# RE-MB-V2_1.net
KiCad netlist of a schematic drawn in EAGLE
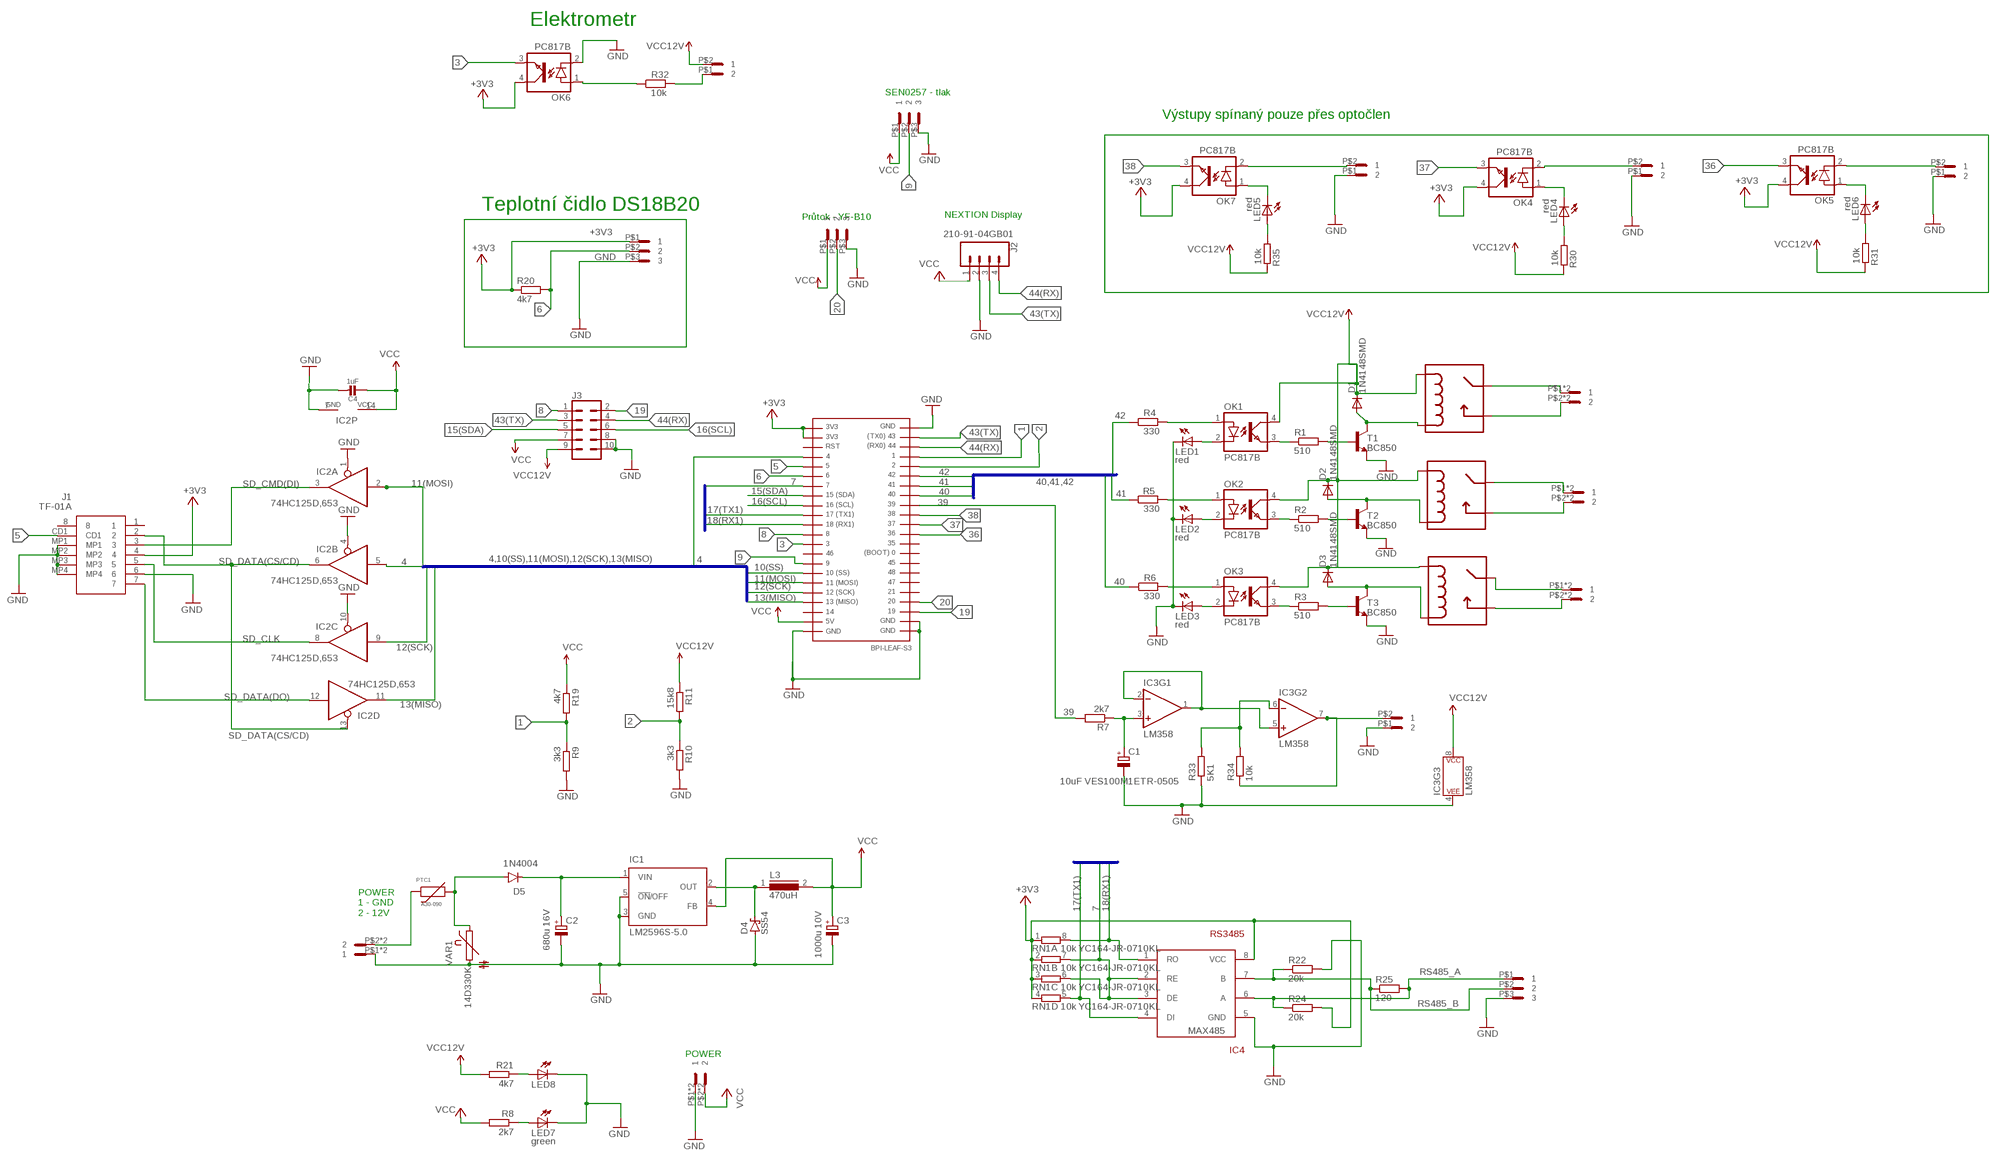
[diagram p0: schematic, sheet 1]

(export (version "E")
  (design (tool "Eeschema 10.0.6"))
  (components
    (comp (ref "BPI")
      (value "BPI-LEAF-S3")
      (footprint "eagle-import:BPI-LEAF-S3")
      (libsource (lib "eagle-import") (part "BPI-LEAF-S3"))
    )
    (comp (ref "C1")
      (value "10uF VES100M1ETR-0505")
      (footprint "eagle-import:PANASONIC_C")
      (libsource (lib "eagle-import") (part "resistor_348_CPOL-EUC"))
    )
    (comp (ref "C2")
      (value "680u 16V")
      (footprint "eagle-import:153CLV-1010")
      (libsource (lib "eagle-import") (part "CPOL-EU153CLV-1010"))
    )
    (comp (ref "C3")
      (value "1000u 10V")
      (footprint "eagle-import:153CLV-1010")
      (libsource (lib "eagle-import") (part "CPOL-EU153CLV-1010"))
    )
    (comp (ref "C4")
      (value "1uF")
      (footprint "eagle-import:0805-NO")
      (libsource (lib "eagle-import") (part "CAP_CERAMIC0805-NOOUTLINE"))
    )
    (comp (ref "D1")
      (value "1N4148SMD")
      (footprint "eagle-import:DO214AC")
      (libsource (lib "eagle-import") (part "1N4148SMD"))
    )
    (comp (ref "D2")
      (value "1N4148SMD")
      (footprint "eagle-import:DO214AC")
      (libsource (lib "eagle-import") (part "1N4148SMD"))
    )
    (comp (ref "D3")
      (value "1N4148SMD")
      (footprint "eagle-import:DO214AC")
      (libsource (lib "eagle-import") (part "1N4148SMD"))
    )
    (comp (ref "D4")
      (value "SS54")
      (footprint "eagle-import:SMB")
      (libsource (lib "eagle-import") (part "MBRS130LT3"))
    )
    (comp (ref "D5")
      (value "1N4004")
      (footprint "eagle-import:DO41-10")
      (libsource (lib "eagle-import") (part "1N4004"))
    )
    (comp (ref "IC1")
      (value "LM2596S-5.0")
      (footprint "eagle-import:TO263-5")
      (fields (field (name "MF") "NATIONAL SEMICONDUCTOR") (field (name "MPN") "LM2596S-ADJ/NOPB"))
      (libsource (lib "eagle-import") (part "LM2596S"))
    )
    (comp (ref "IC2")
      (value "74HC125D,653")
      (footprint "eagle-import:SO14")
      (fields (field (name "SPICEPREFIX") "J"))
      (libsource (lib "eagle-import") (part "74125DHC"))
    )
    (comp (ref "IC3")
      (value "LM358")
      (footprint "eagle-import:SO08")
      (libsource (lib "eagle-import") (part "OPAMP-DUALU"))
    )
    (comp (ref "IC4")
      (value "RS3485")
      (footprint "eagle-import:MAX485")
      (libsource (lib "eagle-import") (part "MAX485MAX485ESA"))
    )
    (comp (ref "J1")
      (value "TF-01A")
      (footprint "eagle-import:TF01A")
      (libsource (lib "eagle-import") (part "TF-01A"))
    )
    (comp (ref "J2")
      (value "210-91-04GB01")
      (footprint "eagle-import:1X04")
      (libsource (lib "eagle-import") (part "CONN_04"))
    )
    (comp (ref "J3")
      (value "CONN_05X2RAF")
      (footprint "eagle-import:2X5-RAF")
      (libsource (lib "eagle-import") (part "CONN_05X2RAF"))
    )
    (comp (ref "K1")
      (value "HF49FD/012-1H11")
      (footprint "eagle-import:HF49FD_024-1H11")
      (libsource (lib "eagle-import") (part "HF49FD/024-1H11"))
    )
    (comp (ref "K2")
      (value "HF49FD/012-1H11")
      (footprint "eagle-import:HF49FD_024-1H11")
      (libsource (lib "eagle-import") (part "HF49FD/024-1H11"))
    )
    (comp (ref "K3")
      (value "HF49FD/012-1H11")
      (footprint "eagle-import:HF49FD_024-1H11")
      (libsource (lib "eagle-import") (part "HF49FD/024-1H11"))
    )
    (comp (ref "L3")
      (value "470uH")
      (footprint "eagle-import:DR127")
      (libsource (lib "eagle-import") (part "DR127"))
    )
    (comp (ref "LED1")
      (value "red")
      (footprint "eagle-import:CHIPLED_0805")
      (libsource (lib "eagle-import") (part "LEDCHIPLED_0805"))
    )
    (comp (ref "LED2")
      (value "red")
      (footprint "eagle-import:CHIPLED_0805")
      (libsource (lib "eagle-import") (part "LEDCHIPLED_0805"))
    )
    (comp (ref "LED3")
      (value "red")
      (footprint "eagle-import:CHIPLED_0805")
      (libsource (lib "eagle-import") (part "LEDCHIPLED_0805"))
    )
    (comp (ref "LED4")
      (value "red")
      (footprint "eagle-import:CHIPLED_0805")
      (libsource (lib "eagle-import") (part "LEDCHIPLED_0805"))
    )
    (comp (ref "LED5")
      (value "red")
      (footprint "eagle-import:CHIPLED_0805")
      (libsource (lib "eagle-import") (part "LEDCHIPLED_0805"))
    )
    (comp (ref "LED6")
      (value "red")
      (footprint "eagle-import:CHIPLED_0805")
      (libsource (lib "eagle-import") (part "LEDCHIPLED_0805"))
    )
    (comp (ref "LED7")
      (value "green")
      (footprint "eagle-import:CHIPLED_0805")
      (libsource (lib "eagle-import") (part "LEDCHIPLED_0805"))
    )
    (comp (ref "LED8")
      (value "green")
      (footprint "eagle-import:CHIPLED_0805")
      (libsource (lib "eagle-import") (part "LEDCHIPLED_0805"))
    )
    (comp (ref "OK1")
      (value "PC817B")
      (footprint "eagle-import:DIL04")
      (fields (field (name "MPN") "PC817X4J000F"))
      (libsource (lib "eagle-import") (part "PC817"))
    )
    (comp (ref "OK2")
      (value "PC817B")
      (footprint "eagle-import:DIL04")
      (fields (field (name "MPN") "PC817X4J000F"))
      (libsource (lib "eagle-import") (part "PC817"))
    )
    (comp (ref "OK3")
      (value "PC817B")
      (footprint "eagle-import:DIL04")
      (fields (field (name "MPN") "PC817X4J000F"))
      (libsource (lib "eagle-import") (part "PC817"))
    )
    (comp (ref "OK4")
      (value "PC817B")
      (footprint "eagle-import:DIL04")
      (fields (field (name "MPN") "PC817X4J000F"))
      (libsource (lib "eagle-import") (part "PC817"))
    )
    (comp (ref "OK5")
      (value "PC817B")
      (footprint "eagle-import:DIL04")
      (fields (field (name "MPN") "PC817X4J000F"))
      (libsource (lib "eagle-import") (part "PC817"))
    )
    (comp (ref "OK6")
      (value "PC817B")
      (footprint "eagle-import:DIL04")
      (fields (field (name "MPN") "PC817X4J000F"))
      (libsource (lib "eagle-import") (part "PC817"))
    )
    (comp (ref "OK7")
      (value "PC817B")
      (footprint "eagle-import:DIL04")
      (fields (field (name "MPN") "PC817X4J000F"))
      (libsource (lib "eagle-import") (part "PC817"))
    )
    (comp (ref "PTC1")
      (value "A30-090")
      (footprint "eagle-import:PK250-240")
      (libsource (lib "eagle-import") (part "TERMISTORPK250-240"))
    )
    (comp (ref "R1")
      (value "510")
      (footprint "eagle-import:M0805")
      (libsource (lib "eagle-import") (part "resistor_348_R-EU_M0805"))
    )
    (comp (ref "R2")
      (value "510")
      (footprint "eagle-import:M0805")
      (libsource (lib "eagle-import") (part "resistor_348_R-EU_M0805"))
    )
    (comp (ref "R3")
      (value "510")
      (footprint "eagle-import:M0805")
      (libsource (lib "eagle-import") (part "resistor_348_R-EU_M0805"))
    )
    (comp (ref "R4")
      (value "330")
      (footprint "eagle-import:M0805")
      (libsource (lib "eagle-import") (part "resistor_348_R-EU_M0805"))
    )
    (comp (ref "R5")
      (value "330")
      (footprint "eagle-import:M0805")
      (libsource (lib "eagle-import") (part "resistor_348_R-EU_M0805"))
    )
    (comp (ref "R6")
      (value "330")
      (footprint "eagle-import:M0805")
      (libsource (lib "eagle-import") (part "resistor_348_R-EU_M0805"))
    )
    (comp (ref "R7")
      (value "2k7")
      (footprint "eagle-import:R0805")
      (libsource (lib "eagle-import") (part "R-EU_R0805"))
    )
    (comp (ref "R8")
      (value "2k7")
      (footprint "eagle-import:M0805")
      (libsource (lib "eagle-import") (part "resistor_348_R-EU_M0805"))
    )
    (comp (ref "R9")
      (value "3k3")
      (footprint "eagle-import:M0805")
      (libsource (lib "eagle-import") (part "resistor_348_R-EU_M0805"))
    )
    (comp (ref "R10")
      (value "3k3")
      (footprint "eagle-import:M0805")
      (libsource (lib "eagle-import") (part "resistor_348_R-EU_M0805"))
    )
    (comp (ref "R11")
      (value "15k8")
      (footprint "eagle-import:M0805")
      (libsource (lib "eagle-import") (part "resistor_348_R-EU_M0805"))
    )
    (comp (ref "R19")
      (value "4k7")
      (footprint "eagle-import:M0805")
      (libsource (lib "eagle-import") (part "resistor_348_R-EU_M0805"))
    )
    (comp (ref "R20")
      (value "4k7")
      (footprint "eagle-import:M0805")
      (libsource (lib "eagle-import") (part "resistor_348_R-EU_M0805"))
    )
    (comp (ref "R21")
      (value "4k7")
      (footprint "eagle-import:M0805")
      (libsource (lib "eagle-import") (part "resistor_348_R-EU_M0805"))
    )
    (comp (ref "R22")
      (value "20k")
      (footprint "eagle-import:R0805")
      (libsource (lib "eagle-import") (part "resistor_348_R-EU_R0805"))
    )
    (comp (ref "R24")
      (value "20k")
      (footprint "eagle-import:R0805")
      (libsource (lib "eagle-import") (part "resistor_348_R-EU_R0805"))
    )
    (comp (ref "R25")
      (value "120")
      (footprint "eagle-import:R0805")
      (libsource (lib "eagle-import") (part "resistor_348_R-EU_R0805"))
    )
    (comp (ref "R30")
      (value "10k")
      (footprint "eagle-import:M0805")
      (libsource (lib "eagle-import") (part "resistor_348_R-EU_M0805"))
    )
    (comp (ref "R31")
      (value "10k")
      (footprint "eagle-import:M0805")
      (libsource (lib "eagle-import") (part "resistor_348_R-EU_M0805"))
    )
    (comp (ref "R32")
      (value "10k")
      (footprint "eagle-import:M0805")
      (libsource (lib "eagle-import") (part "resistor_348_R-EU_M0805"))
    )
    (comp (ref "R33")
      (value "5K1")
      (footprint "eagle-import:R0805")
      (libsource (lib "eagle-import") (part "R-EU_R0805"))
    )
    (comp (ref "R34")
      (value "10k")
      (footprint "eagle-import:R0805")
      (libsource (lib "eagle-import") (part "R-EU_R0805"))
    )
    (comp (ref "R35")
      (value "10k")
      (footprint "eagle-import:M0805")
      (libsource (lib "eagle-import") (part "resistor_348_R-EU_M0805"))
    )
    (comp (ref "RN1")
      (value "10k YC164-JR-0710KL")
      (footprint "eagle-import:0603-ARV")
      (libsource (lib "eagle-import") (part "4R-N0603-ARV"))
    )
    (comp (ref "T1")
      (value "BC850")
      (footprint "eagle-import:SOT23")
      (libsource (lib "eagle-import") (part "BC850"))
    )
    (comp (ref "T2")
      (value "BC850")
      (footprint "eagle-import:SOT23")
      (libsource (lib "eagle-import") (part "BC850"))
    )
    (comp (ref "T3")
      (value "BC850")
      (footprint "eagle-import:SOT23")
      (libsource (lib "eagle-import") (part "BC850"))
    )
    (comp (ref "U$2")
      (value "DG235-5.0")
      (footprint "eagle-import:DG235-5.0")
      (libsource (lib "eagle-import") (part "DG235-5.0"))
    )
    (comp (ref "U$3")
      (value "SPTA1/3-5,0")
      (footprint "eagle-import:SPTA1_3-5,0")
      (libsource (lib "eagle-import") (part "SPTA1/3-5,0"))
    )
    (comp (ref "U$4")
      (value "DG235-5.0")
      (footprint "eagle-import:DG235-5.0")
      (libsource (lib "eagle-import") (part "DG235-5.0"))
    )
    (comp (ref "U$5")
      (value "DG235-5.0")
      (footprint "eagle-import:DG235-5.0")
      (libsource (lib "eagle-import") (part "DG235-5.0"))
    )
    (comp (ref "U$6")
      (value "DG235-5.0")
      (footprint "eagle-import:DG235-5.0")
      (libsource (lib "eagle-import") (part "DG235-5.0"))
    )
    (comp (ref "U$7")
      (value "DG235-5.0")
      (footprint "eagle-import:DG235-5.0")
      (libsource (lib "eagle-import") (part "DG235-5.0"))
    )
    (comp (ref "U$8")
      (value "SPTA1/2-5,0")
      (footprint "eagle-import:SPTA1_2-5,0")
      (libsource (lib "eagle-import") (part "SPTA1/2-5,0"))
    )
    (comp (ref "U$9")
      (value "SPTA1/2-5,0")
      (footprint "eagle-import:SPTA1_2-5,0")
      (libsource (lib "eagle-import") (part "SPTA1/2-5,0"))
    )
    (comp (ref "U$10")
      (value "SPTA1/3-5,0")
      (footprint "eagle-import:SPTA1_3-5,0")
      (libsource (lib "eagle-import") (part "SPTA1/3-5,0"))
    )
    (comp (ref "U$12")
      (value "SPTA1/3-5,0")
      (footprint "eagle-import:SPTA1_3-5,0")
      (libsource (lib "eagle-import") (part "SPTA1/3-5,0"))
    )
    (comp (ref "U$13")
      (value "SPTA1/2-5,0")
      (footprint "eagle-import:SPTA1_2-5,0")
      (libsource (lib "eagle-import") (part "SPTA1/2-5,0"))
    )
    (comp (ref "U$14")
      (value "SPTA1/2-5,0")
      (footprint "eagle-import:SPTA1_2-5,0")
      (libsource (lib "eagle-import") (part "SPTA1/2-5,0"))
    )
    (comp (ref "U$15")
      (value "SPTA1/2-5,0")
      (footprint "eagle-import:SPTA1_2-5,0")
      (libsource (lib "eagle-import") (part "SPTA1/2-5,0"))
    )
    (comp (ref "U$16")
      (value "SPTA1/3-5,0")
      (footprint "eagle-import:SPTA1_3-5,0")
      (libsource (lib "eagle-import") (part "SPTA1/3-5,0"))
    )
    (comp (ref "VAR1")
      (value "14D330K")
      (footprint "eagle-import:S10K11")
      (libsource (lib "eagle-import") (part "S10K11"))
    )
  )
  (nets
    (net (code "1") (name "+3V3") (class "Default")
      (node (ref "BPI") (pin "1") (pinfunction "P$1_1") (pintype "bidirectional"))
      (node (ref "BPI") (pin "2") (pinfunction "P$2_2") (pintype "bidirectional"))
      (node (ref "IC4") (pin "8") (pinfunction "VCC_8") (pintype "bidirectional"))
      (node (ref "J1") (pin "4") (pinfunction "4_4") (pintype "bidirectional"))
      (node (ref "OK4") (pin "4") (pinfunction "COL_4") (pintype "passive"))
      (node (ref "OK5") (pin "4") (pinfunction "COL_4") (pintype "passive"))
      (node (ref "OK6") (pin "4") (pinfunction "COL_4") (pintype "passive"))
      (node (ref "OK7") (pin "4") (pinfunction "COL_4") (pintype "passive"))
      (node (ref "R20") (pin "1") (pinfunction "1_1") (pintype "passive"))
      (node (ref "R24") (pin "2") (pinfunction "2_2") (pintype "passive"))
      (node (ref "RN1") (pin "1") (pinfunction "1_1") (pintype "passive"))
      (node (ref "RN1") (pin "2") (pinfunction "1_2") (pintype "passive"))
      (node (ref "RN1") (pin "3") (pinfunction "1_3") (pintype "passive"))
      (node (ref "RN1") (pin "4") (pinfunction "1_4") (pintype "passive"))
      (node (ref "U$3") (pin "P$1") (pinfunction "1_P$1") (pintype "input"))
    )
    (net (code "2") (name "/4") (class "Default")
      (node (ref "BPI") (pin "4") (pinfunction "P$4_4") (pintype "bidirectional"))
      (node (ref "IC2") (pin "5") (pinfunction "I_5") (pintype "input"))
    )
    (net (code "3") (name "/7") (class "Default")
      (node (ref "BPI") (pin "7") (pinfunction "P$7_7") (pintype "bidirectional"))
      (node (ref "IC4") (pin "2") (pinfunction "RE_2") (pintype "bidirectional"))
      (node (ref "IC4") (pin "3") (pinfunction "DE_3") (pintype "bidirectional"))
      (node (ref "RN1") (pin "6") (pinfunction "2_6") (pintype "passive"))
      (node (ref "RN1") (pin "7") (pinfunction "2_7") (pintype "passive"))
    )
    (net (code "4") (name "/10(SS)") (class "Default")
      (node (ref "BPI") (pin "16") (pinfunction "P$16_16") (pintype "bidirectional"))
    )
    (net (code "5") (name "/11(MOSI)") (class "Default")
      (node (ref "BPI") (pin "17") (pinfunction "P$17_17") (pintype "bidirectional"))
      (node (ref "IC2") (pin "2") (pinfunction "I_2") (pintype "input"))
    )
    (net (code "6") (name "/12(SCK)") (class "Default")
      (node (ref "BPI") (pin "18") (pinfunction "P$18_18") (pintype "bidirectional"))
      (node (ref "IC2") (pin "9") (pinfunction "I_9") (pintype "input"))
    )
    (net (code "7") (name "/13(MISO)") (class "Default")
      (node (ref "BPI") (pin "19") (pinfunction "P$19_19") (pintype "bidirectional"))
      (node (ref "IC2") (pin "11") (pinfunction "O_11") (pintype "tri_state"))
    )
    (net (code "8") (name "/17(TX1)") (class "Default")
      (node (ref "BPI") (pin "10") (pinfunction "P$10_10") (pintype "bidirectional"))
      (node (ref "IC4") (pin "4") (pinfunction "DI_4") (pintype "bidirectional"))
      (node (ref "RN1") (pin "5") (pinfunction "2_5") (pintype "passive"))
    )
    (net (code "9") (name "/18(RX1)") (class "Default")
      (node (ref "BPI") (pin "11") (pinfunction "P$11_11") (pintype "bidirectional"))
      (node (ref "IC4") (pin "1") (pinfunction "RO_1") (pintype "bidirectional"))
      (node (ref "RN1") (pin "8") (pinfunction "2_8") (pintype "passive"))
    )
    (net (code "10") (name "/39") (class "Default")
      (node (ref "BPI") (pin "31") (pinfunction "P$31_31") (pintype "bidirectional"))
      (node (ref "R7") (pin "2") (pinfunction "2_2") (pintype "passive"))
    )
    (net (code "11") (name "/40") (class "Default")
      (node (ref "BPI") (pin "30") (pinfunction "P$30_30") (pintype "bidirectional"))
      (node (ref "R6") (pin "1") (pinfunction "1_1") (pintype "passive"))
    )
    (net (code "12") (name "/41") (class "Default")
      (node (ref "BPI") (pin "29") (pinfunction "P$29_29") (pintype "bidirectional"))
      (node (ref "R5") (pin "1") (pinfunction "1_1") (pintype "passive"))
    )
    (net (code "13") (name "/42") (class "Default")
      (node (ref "BPI") (pin "28") (pinfunction "P$28_28") (pintype "bidirectional"))
      (node (ref "R4") (pin "1") (pinfunction "1_1") (pintype "passive"))
    )
    (net (code "14") (name "/RS485_A") (class "Default")
      (node (ref "IC4") (pin "6") (pinfunction "A_6") (pintype "bidirectional"))
      (node (ref "R24") (pin "1") (pinfunction "1_1") (pintype "passive"))
      (node (ref "R25") (pin "2") (pinfunction "2_2") (pintype "passive"))
      (node (ref "U$10") (pin "P$1") (pinfunction "1_P$1") (pintype "input"))
    )
    (net (code "15") (name "/RS485_B") (class "Default")
      (node (ref "IC4") (pin "7") (pinfunction "B_7") (pintype "bidirectional"))
      (node (ref "R22") (pin "1") (pinfunction "1_1") (pintype "passive"))
      (node (ref "R25") (pin "1") (pinfunction "1_1") (pintype "passive"))
      (node (ref "U$10") (pin "P$2") (pinfunction "2_P$2") (pintype "input"))
    )
    (net (code "16") (name "/SD_CLK") (class "Default")
      (node (ref "IC2") (pin "8") (pinfunction "O_8") (pintype "tri_state"))
      (node (ref "J1") (pin "5") (pinfunction "5_5") (pintype "bidirectional"))
    )
    (net (code "17") (name "/SD_CMD(DI)") (class "Default")
      (node (ref "IC2") (pin "3") (pinfunction "O_3") (pintype "tri_state"))
      (node (ref "J1") (pin "3") (pinfunction "3_3") (pintype "bidirectional"))
    )
    (net (code "18") (name "/SD_DATA(CS{slash}CD)") (class "Default")
      (node (ref "IC2") (pin "13") (pinfunction "OE_13") (pintype "input"))
      (node (ref "IC2") (pin "6") (pinfunction "O_6") (pintype "tri_state"))
      (node (ref "J1") (pin "2") (pinfunction "2_2") (pintype "bidirectional"))
    )
    (net (code "19") (name "/SD_DATA(DO)") (class "Default")
      (node (ref "IC2") (pin "12") (pinfunction "I_12") (pintype "input"))
      (node (ref "J1") (pin "7") (pinfunction "7_7") (pintype "bidirectional"))
    )
    (net (code "23") (name "1") (class "Default")
      (node (ref "BPI") (pin "26") (pinfunction "P$26_26") (pintype "bidirectional"))
      (node (ref "R19") (pin "2") (pinfunction "2_2") (pintype "passive"))
      (node (ref "R9") (pin "1") (pinfunction "1_1") (pintype "passive"))
    )
    (net (code "24") (name "2") (class "Default")
      (node (ref "BPI") (pin "27") (pinfunction "P$27_27") (pintype "bidirectional"))
      (node (ref "R10") (pin "1") (pinfunction "1_1") (pintype "passive"))
      (node (ref "R11") (pin "2") (pinfunction "2_2") (pintype "passive"))
    )
    (net (code "25") (name "3") (class "Default")
      (node (ref "BPI") (pin "13") (pinfunction "P$13_13") (pintype "bidirectional"))
      (node (ref "OK6") (pin "3") (pinfunction "EMIT_3") (pintype "passive"))
    )
    (net (code "26") (name "5") (class "Default")
      (node (ref "BPI") (pin "5") (pinfunction "P$5_5") (pintype "bidirectional"))
      (node (ref "J1") (pin "CD1") (pinfunction "CD1_CD1") (pintype "bidirectional"))
    )
    (net (code "27") (name "6") (class "Default")
      (node (ref "BPI") (pin "6") (pinfunction "P$6_6") (pintype "bidirectional"))
      (node (ref "R20") (pin "2") (pinfunction "2_2") (pintype "passive"))
      (node (ref "U$3") (pin "P$2") (pinfunction "2_P$2") (pintype "input"))
    )
    (net (code "28") (name "8") (class "Default")
      (node (ref "BPI") (pin "12") (pinfunction "P$12_12") (pintype "bidirectional"))
      (node (ref "J3") (pin "1") (pinfunction "1_1") (pintype "passive"))
    )
    (net (code "29") (name "9") (class "Default")
      (node (ref "BPI") (pin "15") (pinfunction "P$15_15") (pintype "bidirectional"))
      (node (ref "U$12") (pin "P$2") (pinfunction "2_P$2") (pintype "input"))
    )
    (net (code "30") (name "15(SDA)") (class "Default")
      (node (ref "BPI") (pin "8") (pinfunction "P$8_8") (pintype "bidirectional"))
      (node (ref "J3") (pin "5") (pinfunction "5_5") (pintype "passive"))
    )
    (net (code "31") (name "16(SCL)") (class "Default")
      (node (ref "BPI") (pin "9") (pinfunction "P$9_9") (pintype "bidirectional"))
      (node (ref "J3") (pin "6") (pinfunction "6_6") (pintype "passive"))
    )
    (net (code "32") (name "19") (class "Default")
      (node (ref "BPI") (pin "42") (pinfunction "P$42_42") (pintype "bidirectional"))
      (node (ref "J3") (pin "2") (pinfunction "2_2") (pintype "passive"))
    )
    (net (code "33") (name "20") (class "Default")
      (node (ref "BPI") (pin "41") (pinfunction "P$41_41") (pintype "bidirectional"))
      (node (ref "U$16") (pin "P$2") (pinfunction "2_P$2") (pintype "input"))
    )
    (net (code "34") (name "36") (class "Default")
      (node (ref "BPI") (pin "34") (pinfunction "P$34_34") (pintype "bidirectional"))
      (node (ref "OK5") (pin "3") (pinfunction "EMIT_3") (pintype "passive"))
    )
    (net (code "35") (name "37") (class "Default")
      (node (ref "BPI") (pin "33") (pinfunction "P$33_33") (pintype "bidirectional"))
      (node (ref "OK4") (pin "3") (pinfunction "EMIT_3") (pintype "passive"))
    )
    (net (code "36") (name "38") (class "Default")
      (node (ref "BPI") (pin "32") (pinfunction "P$32_32") (pintype "bidirectional"))
      (node (ref "OK7") (pin "3") (pinfunction "EMIT_3") (pintype "passive"))
    )
    (net (code "37") (name "43(TX)") (class "Default")
      (node (ref "BPI") (pin "24") (pinfunction "P$24_24") (pintype "bidirectional"))
      (node (ref "J2") (pin "3") (pinfunction "3_3") (pintype "passive"))
      (node (ref "J3") (pin "3") (pinfunction "3_3") (pintype "passive"))
    )
    (net (code "38") (name "44(RX)") (class "Default")
      (node (ref "BPI") (pin "25") (pinfunction "P$25_25") (pintype "bidirectional"))
      (node (ref "J2") (pin "4") (pinfunction "4_4") (pintype "passive"))
      (node (ref "J3") (pin "4") (pinfunction "4_4") (pintype "passive"))
    )
    (net (code "39") (name "GND") (class "Default")
      (node (ref "BPI") (pin "22") (pinfunction "P$22_22") (pintype "bidirectional"))
      (node (ref "BPI") (pin "23") (pinfunction "P$23_23") (pintype "bidirectional"))
      (node (ref "BPI") (pin "43") (pinfunction "P$43_43") (pintype "bidirectional"))
      (node (ref "BPI") (pin "44") (pinfunction "P$44_44") (pintype "bidirectional"))
      (node (ref "C1") (pin "-") (pinfunction "-_-") (pintype "passive"))
      (node (ref "C2") (pin "-") (pinfunction "-_-") (pintype "passive"))
      (node (ref "C3") (pin "-") (pinfunction "-_-") (pintype "passive"))
      (node (ref "C4") (pin "2") (pinfunction "2_2") (pintype "passive"))
      (node (ref "D4") (pin "A") (pinfunction "A_A") (pintype "passive"))
      (node (ref "IC1") (pin "3") (pinfunction "GND_3") (pintype "power_in"))
      (node (ref "IC1") (pin "5") (pinfunction "~{ON}/OFF_5") (pintype "input"))
      (node (ref "IC2") (pin "1") (pinfunction "OE_1") (pintype "input"))
      (node (ref "IC2") (pin "10") (pinfunction "OE_10") (pintype "input"))
      (node (ref "IC2") (pin "4") (pinfunction "OE_4") (pintype "input"))
      (node (ref "IC2") (pin "7") (pinfunction "GND_7") (pintype "power_in"))
      (node (ref "IC3") (pin "4") (pinfunction "P$V-_4") (pintype "bidirectional"))
      (node (ref "IC4") (pin "5") (pinfunction "GND_5") (pintype "bidirectional"))
      (node (ref "J1") (pin "6") (pinfunction "6_6") (pintype "bidirectional"))
      (node (ref "J1") (pin "MP1") (pinfunction "MP1_MP1") (pintype "bidirectional"))
      (node (ref "J1") (pin "MP2") (pinfunction "MP2_MP2") (pintype "bidirectional"))
      (node (ref "J1") (pin "MP3") (pinfunction "MP3_MP3") (pintype "bidirectional"))
      (node (ref "J1") (pin "MP4") (pinfunction "MP4_MP4") (pintype "bidirectional"))
      (node (ref "J2") (pin "2") (pinfunction "2_2") (pintype "passive"))
      (node (ref "J3") (pin "10") (pinfunction "10_10") (pintype "passive"))
      (node (ref "J3") (pin "8") (pinfunction "8_8") (pintype "passive"))
      (node (ref "LED1") (pin "C") (pinfunction "C_C") (pintype "passive"))
      (node (ref "LED2") (pin "C") (pinfunction "C_C") (pintype "passive"))
      (node (ref "LED3") (pin "C") (pinfunction "C_C") (pintype "passive"))
      (node (ref "LED7") (pin "C") (pinfunction "C_C") (pintype "passive"))
      (node (ref "LED8") (pin "C") (pinfunction "C_C") (pintype "passive"))
      (node (ref "OK6") (pin "2") (pinfunction "C_2") (pintype "passive"))
      (node (ref "R10") (pin "2") (pinfunction "2_2") (pintype "passive"))
      (node (ref "R22") (pin "2") (pinfunction "2_2") (pintype "passive"))
      (node (ref "R33") (pin "1") (pinfunction "1_1") (pintype "passive"))
      (node (ref "R9") (pin "2") (pinfunction "2_2") (pintype "passive"))
      (node (ref "T1") (pin "2") (pinfunction "E_2") (pintype "passive"))
      (node (ref "T2") (pin "2") (pinfunction "E_2") (pintype "passive"))
      (node (ref "T3") (pin "2") (pinfunction "E_2") (pintype "passive"))
      (node (ref "U$10") (pin "P$3") (pinfunction "3_P$3") (pintype "input"))
      (node (ref "U$12") (pin "P$3") (pinfunction "3_P$3") (pintype "input"))
      (node (ref "U$13") (pin "P$1") (pinfunction "2_P$1") (pintype "input"))
      (node (ref "U$14") (pin "P$1") (pinfunction "2_P$1") (pintype "input"))
      (node (ref "U$15") (pin "P$1") (pinfunction "2_P$1") (pintype "input"))
      (node (ref "U$16") (pin "P$3") (pinfunction "3_P$3") (pintype "input"))
      (node (ref "U$2") (pin "P$1") (pinfunction "1_P$1") (pintype "input"))
      (node (ref "U$2") (pin "P$3") (pinfunction "1_P$3") (pintype "input"))
      (node (ref "U$3") (pin "P$3") (pinfunction "3_P$3") (pintype "input"))
      (node (ref "U$6") (pin "P$1") (pinfunction "1_P$1") (pintype "input"))
      (node (ref "U$6") (pin "P$3") (pinfunction "1_P$3") (pintype "input"))
      (node (ref "U$8") (pin "P$1") (pinfunction "2_P$1") (pintype "input"))
      (node (ref "VAR1") (pin "2") (pinfunction "2_2") (pintype "passive"))
    )
    (net (code "40") (name "Net-(D5-PadA)") (class "Default")
      (node (ref "D5") (pin "A") (pinfunction "A_A") (pintype "passive"))
      (node (ref "PTC1") (pin "P$2") (pinfunction "P$2_P$2") (pintype "bidirectional"))
      (node (ref "VAR1") (pin "1") (pinfunction "1_1") (pintype "passive"))
    )
    (net (code "41") (name "Net-(IC1-OUT)") (class "Default")
      (node (ref "D4") (pin "C") (pinfunction "C_C") (pintype "passive"))
      (node (ref "IC1") (pin "2") (pinfunction "OUT_2") (pintype "output"))
      (node (ref "L3") (pin "1") (pinfunction "1_1") (pintype "passive"))
    )
    (net (code "42") (name "Net-(IC3A-+IN)") (class "Default")
      (node (ref "C1") (pin "+") (pinfunction "+_+") (pintype "passive"))
      (node (ref "IC3") (pin "3") (pinfunction "+IN_3") (pintype "input"))
      (node (ref "R7") (pin "1") (pinfunction "1_1") (pintype "passive"))
    )
    (net (code "43") (name "Net-(IC3A--IN)") (class "Default")
      (node (ref "IC3") (pin "1") (pinfunction "OUT_1") (pintype "output"))
      (node (ref "IC3") (pin "2") (pinfunction "-IN_2") (pintype "input"))
      (node (ref "IC3") (pin "5") (pinfunction "+IN_5") (pintype "input"))
    )
    (net (code "44") (name "Net-(IC3B--IN)") (class "Default")
      (node (ref "IC3") (pin "6") (pinfunction "-IN_6") (pintype "input"))
      (node (ref "R33") (pin "2") (pinfunction "2_2") (pintype "passive"))
      (node (ref "R34") (pin "2") (pinfunction "2_2") (pintype "passive"))
    )
    (net (code "45") (name "Net-(IC3B-OUT)") (class "Default")
      (node (ref "IC3") (pin "7") (pinfunction "OUT_7") (pintype "output"))
      (node (ref "R34") (pin "1") (pinfunction "1_1") (pintype "passive"))
      (node (ref "U$8") (pin "P$2") (pinfunction "1_P$2") (pintype "input"))
    )
    (net (code "46") (name "Net-(K1-PadP$1)") (class "Default")
      (node (ref "K1") (pin "P$1") (pinfunction "P$1_P$1") (pintype "output"))
      (node (ref "U$4") (pin "P$1") (pinfunction "1_P$1") (pintype "input"))
      (node (ref "U$4") (pin "P$3") (pinfunction "1_P$3") (pintype "input"))
    )
    (net (code "47") (name "Net-(K1-PadP$2)") (class "Default")
      (node (ref "K1") (pin "P$2") (pinfunction "P$2_P$2") (pintype "output"))
      (node (ref "U$4") (pin "P$2") (pinfunction "2_P$2") (pintype "input"))
      (node (ref "U$4") (pin "P$4") (pinfunction "2_P$4") (pintype "input"))
    )
    (net (code "48") (name "Net-(K2-PadP$1)") (class "Default")
      (node (ref "K2") (pin "P$1") (pinfunction "P$1_P$1") (pintype "output"))
      (node (ref "U$5") (pin "P$1") (pinfunction "1_P$1") (pintype "input"))
      (node (ref "U$5") (pin "P$3") (pinfunction "1_P$3") (pintype "input"))
    )
    (net (code "49") (name "Net-(K2-PadP$2)") (class "Default")
      (node (ref "K2") (pin "P$2") (pinfunction "P$2_P$2") (pintype "output"))
      (node (ref "U$5") (pin "P$2") (pinfunction "2_P$2") (pintype "input"))
      (node (ref "U$5") (pin "P$4") (pinfunction "2_P$4") (pintype "input"))
    )
    (net (code "50") (name "Net-(K3-PadP$1)") (class "Default")
      (node (ref "K3") (pin "P$1") (pinfunction "P$1_P$1") (pintype "output"))
      (node (ref "U$7") (pin "P$1") (pinfunction "1_P$1") (pintype "input"))
      (node (ref "U$7") (pin "P$3") (pinfunction "1_P$3") (pintype "input"))
    )
    (net (code "51") (name "Net-(K3-PadP$2)") (class "Default")
      (node (ref "K3") (pin "P$2") (pinfunction "P$2_P$2") (pintype "output"))
      (node (ref "U$7") (pin "P$2") (pinfunction "2_P$2") (pintype "input"))
      (node (ref "U$7") (pin "P$4") (pinfunction "2_P$4") (pintype "input"))
    )
    (net (code "52") (name "Net-(LED4-PadA)") (class "Default")
      (node (ref "LED4") (pin "A") (pinfunction "A_A") (pintype "passive"))
      (node (ref "R30") (pin "1") (pinfunction "1_1") (pintype "passive"))
    )
    (net (code "53") (name "Net-(LED5-PadA)") (class "Default")
      (node (ref "LED5") (pin "A") (pinfunction "A_A") (pintype "passive"))
      (node (ref "R35") (pin "1") (pinfunction "1_1") (pintype "passive"))
    )
    (net (code "54") (name "Net-(LED6-PadA)") (class "Default")
      (node (ref "LED6") (pin "A") (pinfunction "A_A") (pintype "passive"))
      (node (ref "R31") (pin "1") (pinfunction "1_1") (pintype "passive"))
    )
    (net (code "55") (name "Net-(LED7-PadA)") (class "Default")
      (node (ref "LED7") (pin "A") (pinfunction "A_A") (pintype "passive"))
      (node (ref "R8") (pin "1") (pinfunction "1_1") (pintype "passive"))
    )
    (net (code "56") (name "Net-(LED8-PadA)") (class "Default")
      (node (ref "LED8") (pin "A") (pinfunction "A_A") (pintype "passive"))
      (node (ref "R21") (pin "1") (pinfunction "1_1") (pintype "passive"))
    )
    (net (code "57") (name "Net-(OK1-A)") (class "Default")
      (node (ref "OK1") (pin "1") (pinfunction "A_1") (pintype "passive"))
      (node (ref "R4") (pin "2") (pinfunction "2_2") (pintype "passive"))
    )
    (net (code "58") (name "Net-(OK1-C)") (class "Default")
      (node (ref "LED1") (pin "A") (pinfunction "A_A") (pintype "passive"))
      (node (ref "OK1") (pin "2") (pinfunction "C_2") (pintype "passive"))
    )
    (net (code "59") (name "Net-(OK1-EMIT)") (class "Default")
      (node (ref "OK1") (pin "3") (pinfunction "EMIT_3") (pintype "passive"))
      (node (ref "R1") (pin "1") (pinfunction "1_1") (pintype "passive"))
    )
    (net (code "60") (name "Net-(OK2-A)") (class "Default")
      (node (ref "OK2") (pin "1") (pinfunction "A_1") (pintype "passive"))
      (node (ref "R5") (pin "2") (pinfunction "2_2") (pintype "passive"))
    )
    (net (code "61") (name "Net-(OK2-C)") (class "Default")
      (node (ref "LED2") (pin "A") (pinfunction "A_A") (pintype "passive"))
      (node (ref "OK2") (pin "2") (pinfunction "C_2") (pintype "passive"))
    )
    (net (code "62") (name "Net-(OK2-EMIT)") (class "Default")
      (node (ref "OK2") (pin "3") (pinfunction "EMIT_3") (pintype "passive"))
      (node (ref "R2") (pin "1") (pinfunction "1_1") (pintype "passive"))
    )
    (net (code "63") (name "Net-(OK3-A)") (class "Default")
      (node (ref "OK3") (pin "1") (pinfunction "A_1") (pintype "passive"))
      (node (ref "R6") (pin "2") (pinfunction "2_2") (pintype "passive"))
    )
    (net (code "64") (name "Net-(OK3-C)") (class "Default")
      (node (ref "LED3") (pin "A") (pinfunction "A_A") (pintype "passive"))
      (node (ref "OK3") (pin "2") (pinfunction "C_2") (pintype "passive"))
    )
    (net (code "65") (name "Net-(OK3-EMIT)") (class "Default")
      (node (ref "OK3") (pin "3") (pinfunction "EMIT_3") (pintype "passive"))
      (node (ref "R3") (pin "1") (pinfunction "1_1") (pintype "passive"))
    )
    (net (code "66") (name "Net-(OK4-A)") (class "Default")
      (node (ref "LED4") (pin "C") (pinfunction "C_C") (pintype "passive"))
      (node (ref "OK4") (pin "1") (pinfunction "A_1") (pintype "passive"))
    )
    (net (code "67") (name "Net-(OK4-C)") (class "Default")
      (node (ref "OK4") (pin "2") (pinfunction "C_2") (pintype "passive"))
      (node (ref "U$13") (pin "P$2") (pinfunction "1_P$2") (pintype "input"))
    )
    (net (code "68") (name "Net-(OK5-A)") (class "Default")
      (node (ref "LED6") (pin "C") (pinfunction "C_C") (pintype "passive"))
      (node (ref "OK5") (pin "1") (pinfunction "A_1") (pintype "passive"))
    )
    (net (code "69") (name "Net-(OK5-C)") (class "Default")
      (node (ref "OK5") (pin "2") (pinfunction "C_2") (pintype "passive"))
      (node (ref "U$14") (pin "P$2") (pinfunction "1_P$2") (pintype "input"))
    )
    (net (code "70") (name "Net-(OK6-A)") (class "Default")
      (node (ref "OK6") (pin "1") (pinfunction "A_1") (pintype "passive"))
      (node (ref "R32") (pin "1") (pinfunction "1_1") (pintype "passive"))
    )
    (net (code "71") (name "Net-(OK7-A)") (class "Default")
      (node (ref "LED5") (pin "C") (pinfunction "C_C") (pintype "passive"))
      (node (ref "OK7") (pin "1") (pinfunction "A_1") (pintype "passive"))
    )
    (net (code "72") (name "Net-(OK7-C)") (class "Default")
      (node (ref "OK7") (pin "2") (pinfunction "C_2") (pintype "passive"))
      (node (ref "U$15") (pin "P$2") (pinfunction "1_P$2") (pintype "input"))
    )
    (net (code "73") (name "Net-(PTC1-PadP$1)") (class "Default")
      (node (ref "PTC1") (pin "P$1") (pinfunction "P$1_P$1") (pintype "bidirectional"))
      (node (ref "U$2") (pin "P$2") (pinfunction "2_P$2") (pintype "input"))
      (node (ref "U$2") (pin "P$4") (pinfunction "2_P$4") (pintype "input"))
    )
    (net (code "74") (name "Net-(T1-B)") (class "Default")
      (node (ref "R1") (pin "2") (pinfunction "2_2") (pintype "passive"))
      (node (ref "T1") (pin "1") (pinfunction "B_1") (pintype "passive"))
    )
    (net (code "75") (name "Net-(T1-C)") (class "Default")
      (node (ref "D1") (pin "A") (pinfunction "A_A") (pintype "passive"))
      (node (ref "K1") (pin "P$4") (pinfunction "P$4_P$4") (pintype "input"))
      (node (ref "T1") (pin "3") (pinfunction "C_3") (pintype "passive"))
    )
    (net (code "76") (name "Net-(T2-B)") (class "Default")
      (node (ref "R2") (pin "2") (pinfunction "2_2") (pintype "passive"))
      (node (ref "T2") (pin "1") (pinfunction "B_1") (pintype "passive"))
    )
    (net (code "77") (name "Net-(T2-C)") (class "Default")
      (node (ref "D2") (pin "A") (pinfunction "A_A") (pintype "passive"))
      (node (ref "K2") (pin "P$4") (pinfunction "P$4_P$4") (pintype "input"))
      (node (ref "T2") (pin "3") (pinfunction "C_3") (pintype "passive"))
    )
    (net (code "78") (name "Net-(T3-B)") (class "Default")
      (node (ref "R3") (pin "2") (pinfunction "2_2") (pintype "passive"))
      (node (ref "T3") (pin "1") (pinfunction "B_1") (pintype "passive"))
    )
    (net (code "79") (name "Net-(T3-C)") (class "Default")
      (node (ref "D3") (pin "A") (pinfunction "A_A") (pintype "passive"))
      (node (ref "K3") (pin "P$4") (pinfunction "P$4_P$4") (pintype "input"))
      (node (ref "T3") (pin "3") (pinfunction "C_3") (pintype "passive"))
    )
    (net (code "80") (name "Net-(U$9-2)") (class "Default")
      (node (ref "R32") (pin "2") (pinfunction "2_2") (pintype "passive"))
      (node (ref "U$9") (pin "P$1") (pinfunction "2_P$1") (pintype "input"))
    )
    (net (code "81") (name "VCC") (class "Default")
      (node (ref "BPI") (pin "21") (pinfunction "P$21_21") (pintype "bidirectional"))
      (node (ref "C3") (pin "+") (pinfunction "+_+") (pintype "passive"))
      (node (ref "C4") (pin "1") (pinfunction "1_1") (pintype "passive"))
      (node (ref "IC1") (pin "4") (pinfunction "FB_4") (pintype "input"))
      (node (ref "IC2") (pin "14") (pinfunction "VCC_14") (pintype "power_in"))
      (node (ref "J2") (pin "1") (pinfunction "1_1") (pintype "passive"))
      (node (ref "J3") (pin "7") (pinfunction "7_7") (pintype "passive"))
      (node (ref "L3") (pin "2") (pinfunction "2_2") (pintype "passive"))
      (node (ref "R19") (pin "1") (pinfunction "1_1") (pintype "passive"))
      (node (ref "R8") (pin "2") (pinfunction "2_2") (pintype "passive"))
      (node (ref "U$12") (pin "P$1") (pinfunction "1_P$1") (pintype "input"))
      (node (ref "U$16") (pin "P$1") (pinfunction "1_P$1") (pintype "input"))
      (node (ref "U$6") (pin "P$2") (pinfunction "2_P$2") (pintype "input"))
      (node (ref "U$6") (pin "P$4") (pinfunction "2_P$4") (pintype "input"))
    )
    (net (code "82") (name "VCC12V") (class "Default")
      (node (ref "C2") (pin "+") (pinfunction "+_+") (pintype "passive"))
      (node (ref "D1") (pin "C") (pinfunction "C_C") (pintype "passive"))
      (node (ref "D2") (pin "C") (pinfunction "C_C") (pintype "passive"))
      (node (ref "D3") (pin "C") (pinfunction "C_C") (pintype "passive"))
      (node (ref "D5") (pin "C") (pinfunction "C_C") (pintype "passive"))
      (node (ref "IC1") (pin "1") (pinfunction "VIN_1") (pintype "input"))
      (node (ref "IC3") (pin "8") (pinfunction "P$V+_8") (pintype "bidirectional"))
      (node (ref "J3") (pin "9") (pinfunction "9_9") (pintype "passive"))
      (node (ref "K1") (pin "P$3") (pinfunction "P$3_P$3") (pintype "input"))
      (node (ref "K2") (pin "P$3") (pinfunction "P$3_P$3") (pintype "input"))
      (node (ref "K3") (pin "P$3") (pinfunction "P$3_P$3") (pintype "input"))
      (node (ref "OK1") (pin "4") (pinfunction "COL_4") (pintype "passive"))
      (node (ref "OK2") (pin "4") (pinfunction "COL_4") (pintype "passive"))
      (node (ref "OK3") (pin "4") (pinfunction "COL_4") (pintype "passive"))
      (node (ref "R11") (pin "1") (pinfunction "1_1") (pintype "passive"))
      (node (ref "R21") (pin "2") (pinfunction "2_2") (pintype "passive"))
      (node (ref "R30") (pin "2") (pinfunction "2_2") (pintype "passive"))
      (node (ref "R31") (pin "2") (pinfunction "2_2") (pintype "passive"))
      (node (ref "R35") (pin "2") (pinfunction "2_2") (pintype "passive"))
      (node (ref "U$9") (pin "P$2") (pinfunction "1_P$2") (pintype "input"))
    )
    (net (code "83") (name "unconnected-(BPI-P$3-Pad3)") (class "Default")
      (node (ref "BPI") (pin "3") (pinfunction "P$3_3") (pintype "bidirectional"))
    )
    (net (code "84") (name "unconnected-(BPI-P$14-Pad14)") (class "Default")
      (node (ref "BPI") (pin "14") (pinfunction "P$14_14") (pintype "bidirectional"))
    )
    (net (code "85") (name "unconnected-(BPI-P$20-Pad20)") (class "Default")
      (node (ref "BPI") (pin "20") (pinfunction "P$20_20") (pintype "bidirectional"))
    )
    (net (code "86") (name "unconnected-(BPI-P$35-Pad35)") (class "Default")
      (node (ref "BPI") (pin "35") (pinfunction "P$35_35") (pintype "bidirectional"))
    )
    (net (code "87") (name "unconnected-(BPI-P$36-Pad36)") (class "Default")
      (node (ref "BPI") (pin "36") (pinfunction "P$36_36") (pintype "bidirectional"))
    )
    (net (code "88") (name "unconnected-(BPI-P$37-Pad37)") (class "Default")
      (node (ref "BPI") (pin "37") (pinfunction "P$37_37") (pintype "bidirectional"))
    )
    (net (code "89") (name "unconnected-(BPI-P$38-Pad38)") (class "Default")
      (node (ref "BPI") (pin "38") (pinfunction "P$38_38") (pintype "bidirectional"))
    )
    (net (code "90") (name "unconnected-(BPI-P$39-Pad39)") (class "Default")
      (node (ref "BPI") (pin "39") (pinfunction "P$39_39") (pintype "bidirectional"))
    )
    (net (code "91") (name "unconnected-(BPI-P$40-Pad40)") (class "Default")
      (node (ref "BPI") (pin "40") (pinfunction "P$40_40") (pintype "bidirectional"))
    )
    (net (code "92") (name "unconnected-(J1-Pad1)") (class "Default")
      (node (ref "J1") (pin "1") (pinfunction "1_1") (pintype "bidirectional"))
    )
    (net (code "93") (name "unconnected-(J1-Pad8)") (class "Default")
      (node (ref "J1") (pin "8") (pinfunction "8_8") (pintype "bidirectional"))
    )
  )
)
